# SCH_semi-automatic-healing-reminder_2026.net
KiCad netlist of a schematic drawn in EasyEDA
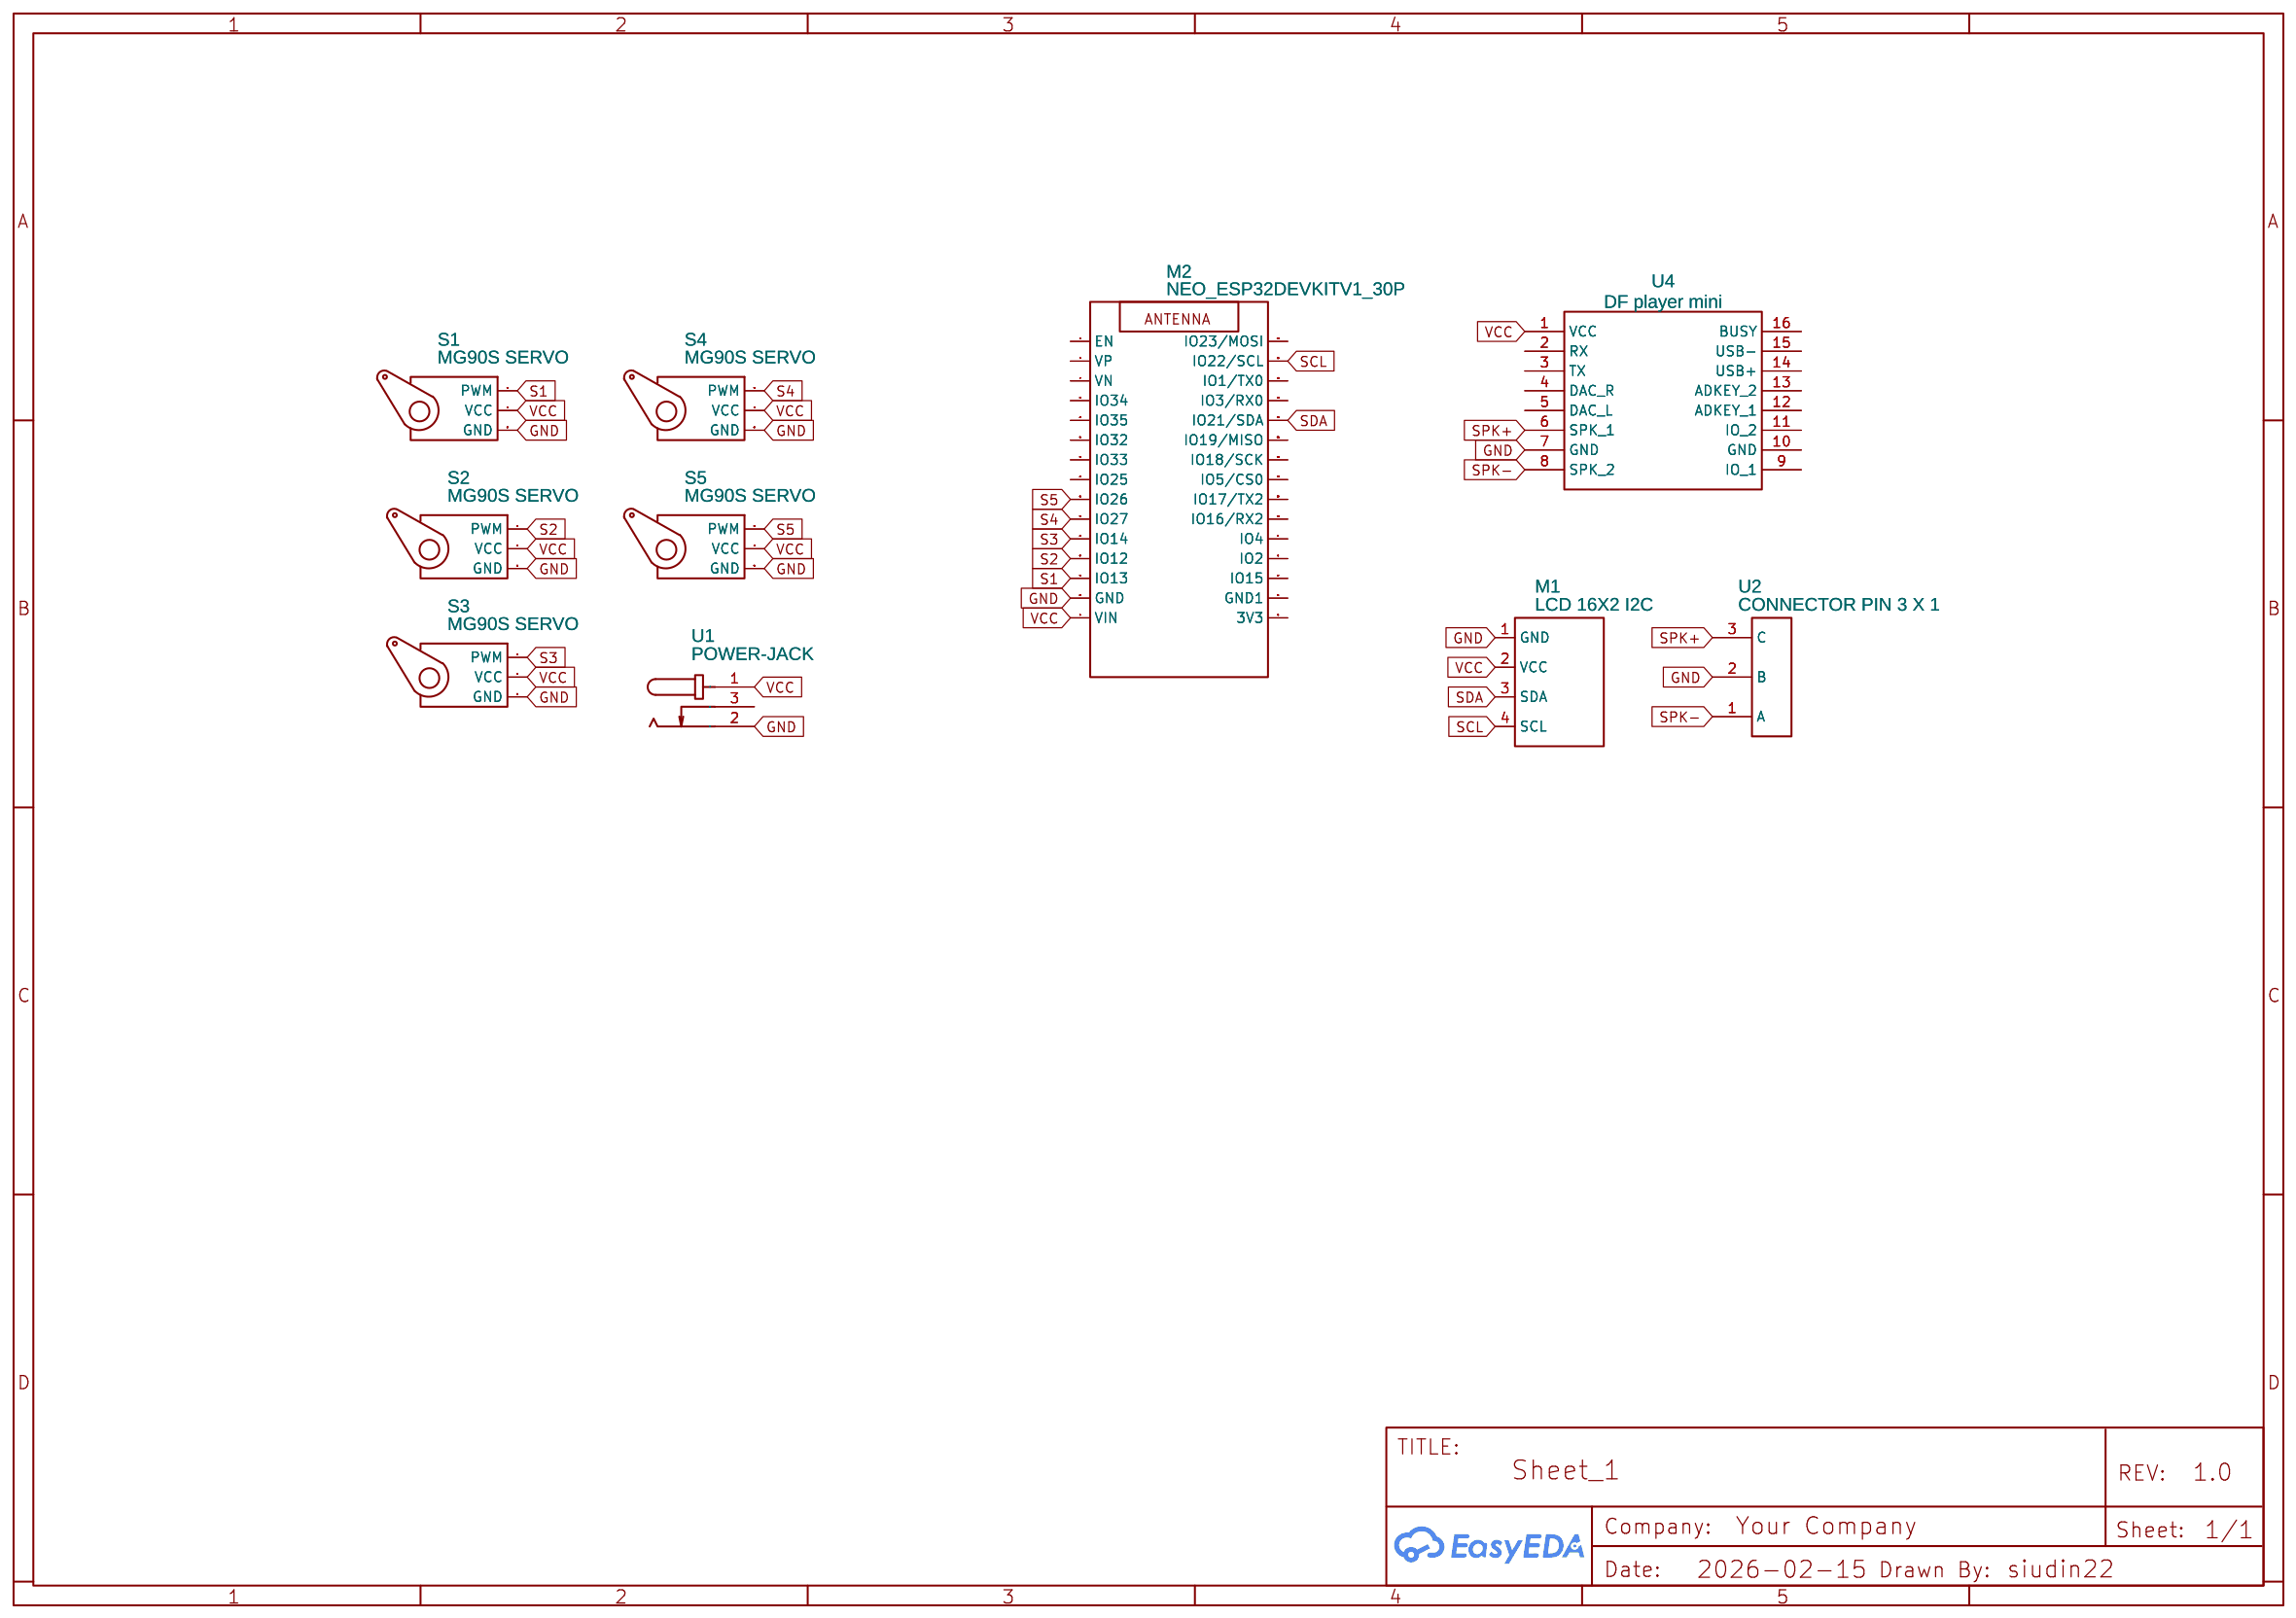
[diagram p0: schematic sheet]

(export (version "E")
  (design (tool "Eeschema 10.0.6"))
  (components
    (comp (ref "M1") (value "LCD 16X2 I2C") (libsource (lib "") (part "LCD 16X2 I2C")))
    (comp (ref "M2") (value "NEO_ESP32DEVKITV1_30P") (libsource (lib "") (part "NEO_ESP32DEVKITV1_30P")))
    (comp (ref "S1") (value "MG90S SERVO") (libsource (lib "") (part "MG90S SERVO_1")))
    (comp (ref "S2") (value "MG90S SERVO") (libsource (lib "") (part "MG90S SERVO_1")))
    (comp (ref "S3") (value "MG90S SERVO") (libsource (lib "") (part "MG90S SERVO_1")))
    (comp (ref "S4") (value "MG90S SERVO") (libsource (lib "") (part "MG90S SERVO")))
    (comp (ref "S5") (value "MG90S SERVO") (libsource (lib "") (part "MG90S SERVO")))
    (comp (ref "U1")
      (value "POWER-JACK")
      (fields (field (name "Manufacturer") "索峰"))
      (libsource (lib "") (part "POWER-JACK"))
    )
    (comp (ref "U2") (value "CONNECTOR PIN 3 X 1") (libsource (lib "") (part "CONNECTOR PIN 3 X 1")))
    (comp (ref "U4") (value "DF player mini") (libsource (lib "") (part "DF player mini")))
  )
  (nets
    (net (code "1") (name "GND") (class "Default")
      (node (ref "M1") (pin "1") (pinfunction "GND_1") (pintype "unspecified"))
      (node (ref "M2") (pin "GND") (pinfunction "GND_GND") (pintype "bidirectional"))
      (node (ref "S1") (pin "GND") (pinfunction "GND_GND") (pintype "input"))
      (node (ref "S2") (pin "GND") (pinfunction "GND_GND") (pintype "input"))
      (node (ref "S3") (pin "GND") (pinfunction "GND_GND") (pintype "input"))
      (node (ref "S4") (pin "GND") (pinfunction "GND_GND") (pintype "input"))
      (node (ref "S5") (pin "GND") (pinfunction "GND_GND") (pintype "input"))
      (node (ref "U1") (pin "2") (pinfunction "2_2") (pintype "unspecified"))
      (node (ref "U2") (pin "2") (pinfunction "B_2") (pintype "unspecified"))
      (node (ref "U4") (pin "7") (pinfunction "GND_7") (pintype "unspecified"))
    )
    (net (code "2") (name "S1") (class "Default")
      (node (ref "M2") (pin "IO13") (pinfunction "IO13_IO13") (pintype "bidirectional"))
      (node (ref "S1") (pin "PWM") (pinfunction "PWM_PWM") (pintype "input"))
    )
    (net (code "3") (name "S2") (class "Default")
      (node (ref "M2") (pin "IO12") (pinfunction "IO12_IO12") (pintype "bidirectional"))
      (node (ref "S2") (pin "PWM") (pinfunction "PWM_PWM") (pintype "input"))
    )
    (net (code "4") (name "S3") (class "Default")
      (node (ref "M2") (pin "IO14") (pinfunction "IO14_IO14") (pintype "bidirectional"))
      (node (ref "S3") (pin "PWM") (pinfunction "PWM_PWM") (pintype "input"))
    )
    (net (code "5") (name "S4") (class "Default")
      (node (ref "M2") (pin "IO27") (pinfunction "IO27_IO27") (pintype "bidirectional"))
      (node (ref "S4") (pin "PWM") (pinfunction "PWM_PWM") (pintype "input"))
    )
    (net (code "6") (name "S5") (class "Default")
      (node (ref "M2") (pin "IO26") (pinfunction "IO26_IO26") (pintype "bidirectional"))
      (node (ref "S5") (pin "PWM") (pinfunction "PWM_PWM") (pintype "input"))
    )
    (net (code "7") (name "SCL") (class "Default")
      (node (ref "M1") (pin "4") (pinfunction "SCL_4") (pintype "unspecified"))
      (node (ref "M2") (pin "IO22/SCL") (pinfunction "IO22/SCL_IO22/SCL") (pintype "bidirectional"))
    )
    (net (code "8") (name "SDA") (class "Default")
      (node (ref "M1") (pin "3") (pinfunction "SDA_3") (pintype "unspecified"))
      (node (ref "M2") (pin "IO21/SDA") (pinfunction "IO21/SDA_IO21/SDA") (pintype "bidirectional"))
    )
    (net (code "9") (name "SPK+") (class "Default")
      (node (ref "U2") (pin "3") (pinfunction "C_3") (pintype "unspecified"))
      (node (ref "U4") (pin "6") (pinfunction "SPK_1_6") (pintype "unspecified"))
    )
    (net (code "10") (name "SPK-") (class "Default")
      (node (ref "U2") (pin "1") (pinfunction "A_1") (pintype "unspecified"))
      (node (ref "U4") (pin "8") (pinfunction "SPK_2_8") (pintype "unspecified"))
    )
    (net (code "11") (name "VCC") (class "Default")
      (node (ref "M1") (pin "2") (pinfunction "VCC_2") (pintype "unspecified"))
      (node (ref "M2") (pin "VIN") (pinfunction "VIN_VIN") (pintype "bidirectional"))
      (node (ref "S1") (pin "VCC") (pinfunction "VCC_VCC") (pintype "input"))
      (node (ref "S2") (pin "VCC") (pinfunction "VCC_VCC") (pintype "input"))
      (node (ref "S3") (pin "VCC") (pinfunction "VCC_VCC") (pintype "input"))
      (node (ref "S4") (pin "VCC") (pinfunction "VCC_VCC") (pintype "input"))
      (node (ref "S5") (pin "VCC") (pinfunction "VCC_VCC") (pintype "input"))
      (node (ref "U1") (pin "1") (pinfunction "1_1") (pintype "unspecified"))
      (node (ref "U4") (pin "1") (pinfunction "VCC_1") (pintype "unspecified"))
    )
    (net (code "12") (name "unconnected-(M2-Pad3V3)") (class "Default")
      (node (ref "M2") (pin "3V3") (pinfunction "3V3_3V3") (pintype "bidirectional"))
    )
    (net (code "13") (name "unconnected-(M2-PadEN)") (class "Default")
      (node (ref "M2") (pin "EN") (pinfunction "EN_EN") (pintype "bidirectional"))
    )
    (net (code "14") (name "unconnected-(M2-PadGND1)") (class "Default")
      (node (ref "M2") (pin "GND1") (pinfunction "GND1_GND1") (pintype "bidirectional"))
    )
    (net (code "15") (name "unconnected-(M2-PadIO1{slash}TX0)") (class "Default")
      (node (ref "M2") (pin "IO1/TX0") (pinfunction "IO1/TX0_IO1/TX0") (pintype "bidirectional"))
    )
    (net (code "16") (name "unconnected-(M2-PadIO2)") (class "Default")
      (node (ref "M2") (pin "IO2") (pinfunction "IO2_IO2") (pintype "bidirectional"))
    )
    (net (code "17") (name "unconnected-(M2-PadIO3{slash}RX0)") (class "Default")
      (node (ref "M2") (pin "IO3/RX0") (pinfunction "IO3/RX0_IO3/RX0") (pintype "bidirectional"))
    )
    (net (code "18") (name "unconnected-(M2-PadIO4)") (class "Default")
      (node (ref "M2") (pin "IO4") (pinfunction "IO4_IO4") (pintype "bidirectional"))
    )
    (net (code "19") (name "unconnected-(M2-PadIO5{slash}CS0)") (class "Default")
      (node (ref "M2") (pin "IO5/CS0") (pinfunction "IO5/CS0_IO5/CS0") (pintype "bidirectional"))
    )
    (net (code "20") (name "unconnected-(M2-PadIO15)") (class "Default")
      (node (ref "M2") (pin "IO15") (pinfunction "IO15_IO15") (pintype "bidirectional"))
    )
    (net (code "21") (name "unconnected-(M2-PadIO16{slash}RX2)") (class "Default")
      (node (ref "M2") (pin "IO16/RX2") (pinfunction "IO16/RX2_IO16/RX2") (pintype "bidirectional"))
    )
    (net (code "22") (name "unconnected-(M2-PadIO17{slash}TX2)") (class "Default")
      (node (ref "M2") (pin "IO17/TX2") (pinfunction "IO17/TX2_IO17/TX2") (pintype "bidirectional"))
    )
    (net (code "23") (name "unconnected-(M2-PadIO18{slash}SCK)") (class "Default")
      (node (ref "M2") (pin "IO18/SCK") (pinfunction "IO18/SCK_IO18/SCK") (pintype "bidirectional"))
    )
    (net (code "24") (name "unconnected-(M2-PadIO19{slash}MISO)") (class "Default")
      (node (ref "M2") (pin "IO19/MISO") (pinfunction "IO19/MISO_IO19/MISO") (pintype "bidirectional"))
    )
    (net (code "25") (name "unconnected-(M2-PadIO23{slash}MOSI)") (class "Default")
      (node (ref "M2") (pin "IO23/MOSI") (pinfunction "IO23/MOSI_IO23/MOSI") (pintype "bidirectional"))
    )
    (net (code "26") (name "unconnected-(M2-PadIO25)") (class "Default")
      (node (ref "M2") (pin "IO25") (pinfunction "IO25_IO25") (pintype "bidirectional"))
    )
    (net (code "27") (name "unconnected-(M2-PadIO32)") (class "Default")
      (node (ref "M2") (pin "IO32") (pinfunction "IO32_IO32") (pintype "bidirectional"))
    )
    (net (code "28") (name "unconnected-(M2-PadIO33)") (class "Default")
      (node (ref "M2") (pin "IO33") (pinfunction "IO33_IO33") (pintype "bidirectional"))
    )
    (net (code "29") (name "unconnected-(M2-PadIO34)") (class "Default")
      (node (ref "M2") (pin "IO34") (pinfunction "IO34_IO34") (pintype "bidirectional"))
    )
    (net (code "30") (name "unconnected-(M2-PadIO35)") (class "Default")
      (node (ref "M2") (pin "IO35") (pinfunction "IO35_IO35") (pintype "bidirectional"))
    )
    (net (code "31") (name "unconnected-(M2-PadVN)") (class "Default")
      (node (ref "M2") (pin "VN") (pinfunction "VN_VN") (pintype "bidirectional"))
    )
    (net (code "32") (name "unconnected-(M2-PadVP)") (class "Default")
      (node (ref "M2") (pin "VP") (pinfunction "VP_VP") (pintype "bidirectional"))
    )
    (net (code "33") (name "unconnected-(U1-Pad3)") (class "Default")
      (node (ref "U1") (pin "3") (pinfunction "3_3") (pintype "unspecified"))
    )
    (net (code "34") (name "unconnected-(U4-ADKEY_1-Pad12)") (class "Default")
      (node (ref "U4") (pin "12") (pinfunction "ADKEY_1_12") (pintype "unspecified"))
    )
    (net (code "35") (name "unconnected-(U4-ADKEY_2-Pad13)") (class "Default")
      (node (ref "U4") (pin "13") (pinfunction "ADKEY_2_13") (pintype "unspecified"))
    )
    (net (code "36") (name "unconnected-(U4-BUSY-Pad16)") (class "Default")
      (node (ref "U4") (pin "16") (pinfunction "BUSY_16") (pintype "unspecified"))
    )
    (net (code "37") (name "unconnected-(U4-DAC_L-Pad5)") (class "Default")
      (node (ref "U4") (pin "5") (pinfunction "DAC_L_5") (pintype "unspecified"))
    )
    (net (code "38") (name "unconnected-(U4-DAC_R-Pad4)") (class "Default")
      (node (ref "U4") (pin "4") (pinfunction "DAC_R_4") (pintype "unspecified"))
    )
    (net (code "39") (name "unconnected-(U4-GND-Pad10)") (class "Default")
      (node (ref "U4") (pin "10") (pinfunction "GND_10") (pintype "unspecified"))
    )
    (net (code "40") (name "unconnected-(U4-IO_1-Pad9)") (class "Default")
      (node (ref "U4") (pin "9") (pinfunction "IO_1_9") (pintype "unspecified"))
    )
    (net (code "41") (name "unconnected-(U4-IO_2-Pad11)") (class "Default")
      (node (ref "U4") (pin "11") (pinfunction "IO_2_11") (pintype "unspecified"))
    )
    (net (code "42") (name "unconnected-(U4-RX-Pad2)") (class "Default")
      (node (ref "U4") (pin "2") (pinfunction "RX_2") (pintype "unspecified"))
    )
    (net (code "43") (name "unconnected-(U4-TX-Pad3)") (class "Default")
      (node (ref "U4") (pin "3") (pinfunction "TX_3") (pintype "unspecified"))
    )
    (net (code "44") (name "unconnected-(U4-USB+-Pad14)") (class "Default")
      (node (ref "U4") (pin "14") (pinfunction "USB+_14") (pintype "unspecified"))
    )
    (net (code "45") (name "unconnected-(U4-USB--Pad15)") (class "Default")
      (node (ref "U4") (pin "15") (pinfunction "USB-_15") (pintype "unspecified"))
    )
  )
)
